# light_sensors.net
KiCad netlist of a schematic drawn in EAGLE
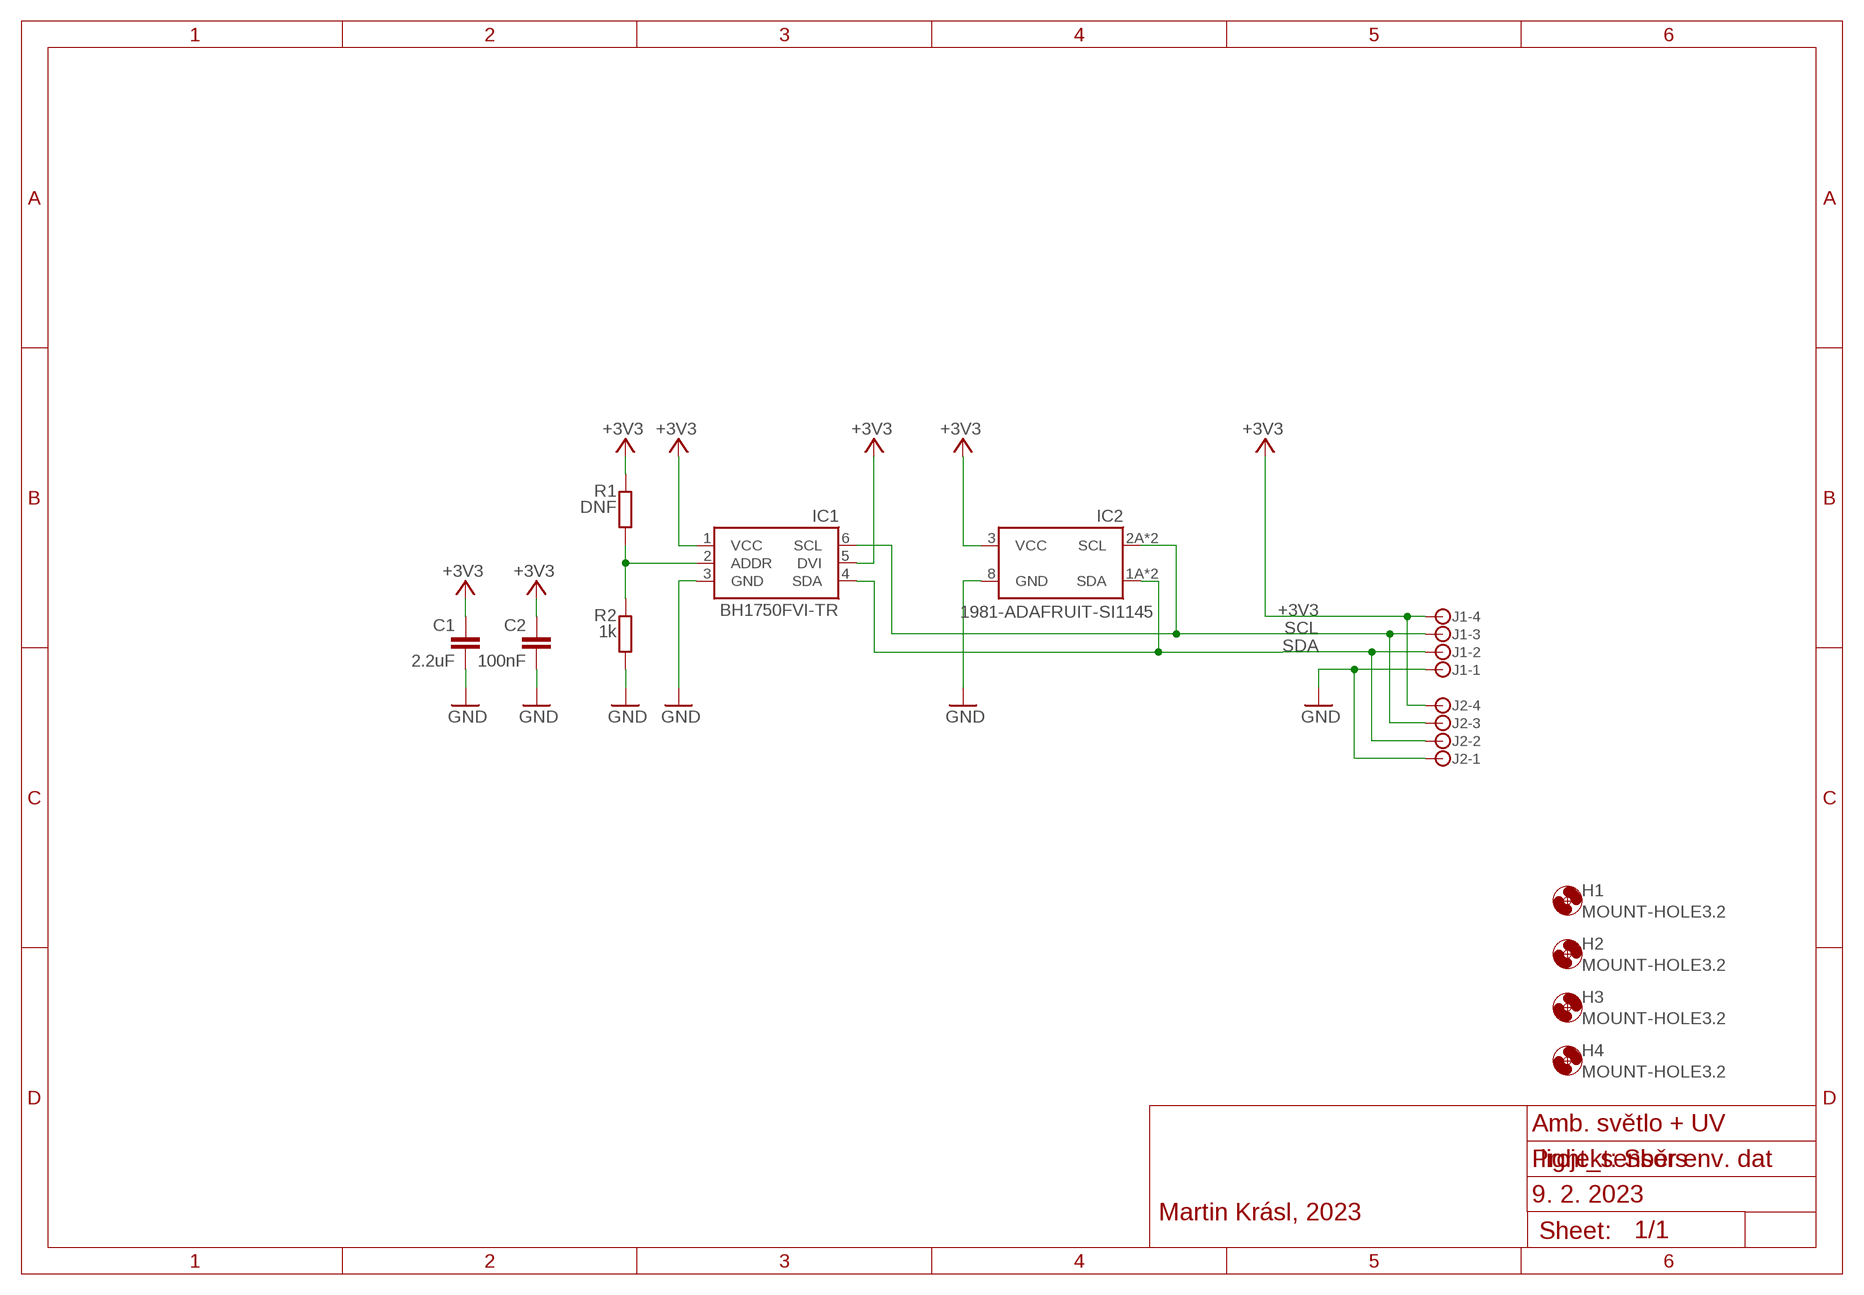
[diagram p0: schematic, sheet 1]

(export (version "E")
  (design (tool "Eeschema 10.0.6"))
  (components
    (comp (ref "C1")
      (value "2.2uF")
      (footprint "eagle-import:C0805")
      (libsource (lib "eagle-import") (part "C-EUC0805"))
    )
    (comp (ref "C2")
      (value "100nF")
      (footprint "eagle-import:C0402")
      (libsource (lib "eagle-import") (part "C-EUC0402"))
    )
    (comp (ref "H1")
      (value "MOUNT-HOLE3.2")
      (footprint "eagle-import:3,2")
      (libsource (lib "eagle-import") (part "MOUNT-HOLE3.2"))
    )
    (comp (ref "H2")
      (value "MOUNT-HOLE3.2")
      (footprint "eagle-import:3,2")
      (libsource (lib "eagle-import") (part "MOUNT-HOLE3.2"))
    )
    (comp (ref "H3")
      (value "MOUNT-HOLE3.2")
      (footprint "eagle-import:3,2")
      (libsource (lib "eagle-import") (part "MOUNT-HOLE3.2"))
    )
    (comp (ref "H4")
      (value "MOUNT-HOLE3.2")
      (footprint "eagle-import:3,2")
      (libsource (lib "eagle-import") (part "MOUNT-HOLE3.2"))
    )
    (comp (ref "IC1")
      (value "BH1750FVI-TR")
      (footprint "eagle-import:WSOF6")
      (fields (field (name "MOUSER_PART_NUMBER") "755-BH1750FVI-TR"))
      (libsource (lib "eagle-import") (part "BH1750FVI-TR"))
    )
    (comp (ref "IC2")
      (value "1981-ADAFRUIT-SI1145")
      (footprint "eagle-import:1981-ADAFRUIT-SI1145")
      (fields
        (field (name "ARROW_PART_NUMBER") "BH1750FVI-TR")
        (field (name "MOUSER_PART_NUMBER") "755-BH1750FVI-TR")
      )
      (libsource (lib "eagle-import") (part "1981-ADAFRUIT-SI1145"))
    )
    (comp (ref "J1")
      (value "JST-XH-4")
      (footprint "eagle-import:B4B-XH-A")
      (fields (field (name "MF") "JST") (field (name "MPN") "B4B-XH-A"))
      (libsource (lib "eagle-import") (part "JST-XH-4"))
    )
    (comp (ref "J2")
      (value "JST-XH-4")
      (footprint "eagle-import:B4B-XH-A")
      (fields (field (name "MF") "JST") (field (name "MPN") "B4B-XH-A"))
      (libsource (lib "eagle-import") (part "JST-XH-4"))
    )
    (comp (ref "R1")
      (value "DNF")
      (footprint "eagle-import:R0402")
      (libsource (lib "eagle-import") (part "R-EU_R0402"))
    )
    (comp (ref "R2")
      (value "1k")
      (footprint "eagle-import:R0402")
      (libsource (lib "eagle-import") (part "R-EU_R0402"))
    )
  )
  (nets
    (net (code "1") (name "+3V3") (class "Default")
      (node (ref "C1") (pin "1") (pinfunction "1_1") (pintype "passive"))
      (node (ref "C2") (pin "1") (pinfunction "1_1") (pintype "passive"))
      (node (ref "IC1") (pin "1") (pinfunction "VCC_1") (pintype "bidirectional"))
      (node (ref "IC1") (pin "5") (pinfunction "DVI_5") (pintype "bidirectional"))
      (node (ref "IC2") (pin "3") (pinfunction "VCC_3") (pintype "bidirectional"))
      (node (ref "J1") (pin "4") (pinfunction "P_4") (pintype "bidirectional"))
      (node (ref "J2") (pin "4") (pinfunction "P_4") (pintype "bidirectional"))
      (node (ref "R1") (pin "2") (pinfunction "2_2") (pintype "passive"))
    )
    (net (code "2") (name "/SCL") (class "Default")
      (node (ref "IC1") (pin "6") (pinfunction "SCL_6") (pintype "bidirectional"))
      (node (ref "IC2") (pin "2A") (pinfunction "SCL_2A") (pintype "bidirectional"))
      (node (ref "IC2") (pin "2B") (pinfunction "SCL_2B") (pintype "bidirectional"))
      (node (ref "J1") (pin "3") (pinfunction "P_3") (pintype "bidirectional"))
      (node (ref "J2") (pin "3") (pinfunction "P_3") (pintype "bidirectional"))
    )
    (net (code "3") (name "/SDA") (class "Default")
      (node (ref "IC1") (pin "4") (pinfunction "SDA_4") (pintype "bidirectional"))
      (node (ref "IC2") (pin "1A") (pinfunction "SDA_1A") (pintype "bidirectional"))
      (node (ref "IC2") (pin "1B") (pinfunction "SDA_1B") (pintype "bidirectional"))
      (node (ref "J1") (pin "2") (pinfunction "P_2") (pintype "bidirectional"))
      (node (ref "J2") (pin "2") (pinfunction "P_2") (pintype "bidirectional"))
    )
    (net (code "4") (name "GND") (class "Default")
      (node (ref "C1") (pin "2") (pinfunction "2_2") (pintype "passive"))
      (node (ref "C2") (pin "2") (pinfunction "2_2") (pintype "passive"))
      (node (ref "IC1") (pin "3") (pinfunction "GND_3") (pintype "bidirectional"))
      (node (ref "IC2") (pin "8") (pinfunction "GND_8") (pintype "bidirectional"))
      (node (ref "J1") (pin "1") (pinfunction "P_1") (pintype "bidirectional"))
      (node (ref "J2") (pin "1") (pinfunction "P_1") (pintype "bidirectional"))
      (node (ref "R2") (pin "1") (pinfunction "1_1") (pintype "passive"))
    )
    (net (code "5") (name "Net-(IC1-ADDR)") (class "Default")
      (node (ref "IC1") (pin "2") (pinfunction "ADDR_2") (pintype "bidirectional"))
      (node (ref "R1") (pin "1") (pinfunction "1_1") (pintype "passive"))
      (node (ref "R2") (pin "2") (pinfunction "2_2") (pintype "passive"))
    )
  )
)
